# 2_POWER.net
KiCad netlist of a schematic drawn in Altium Designer
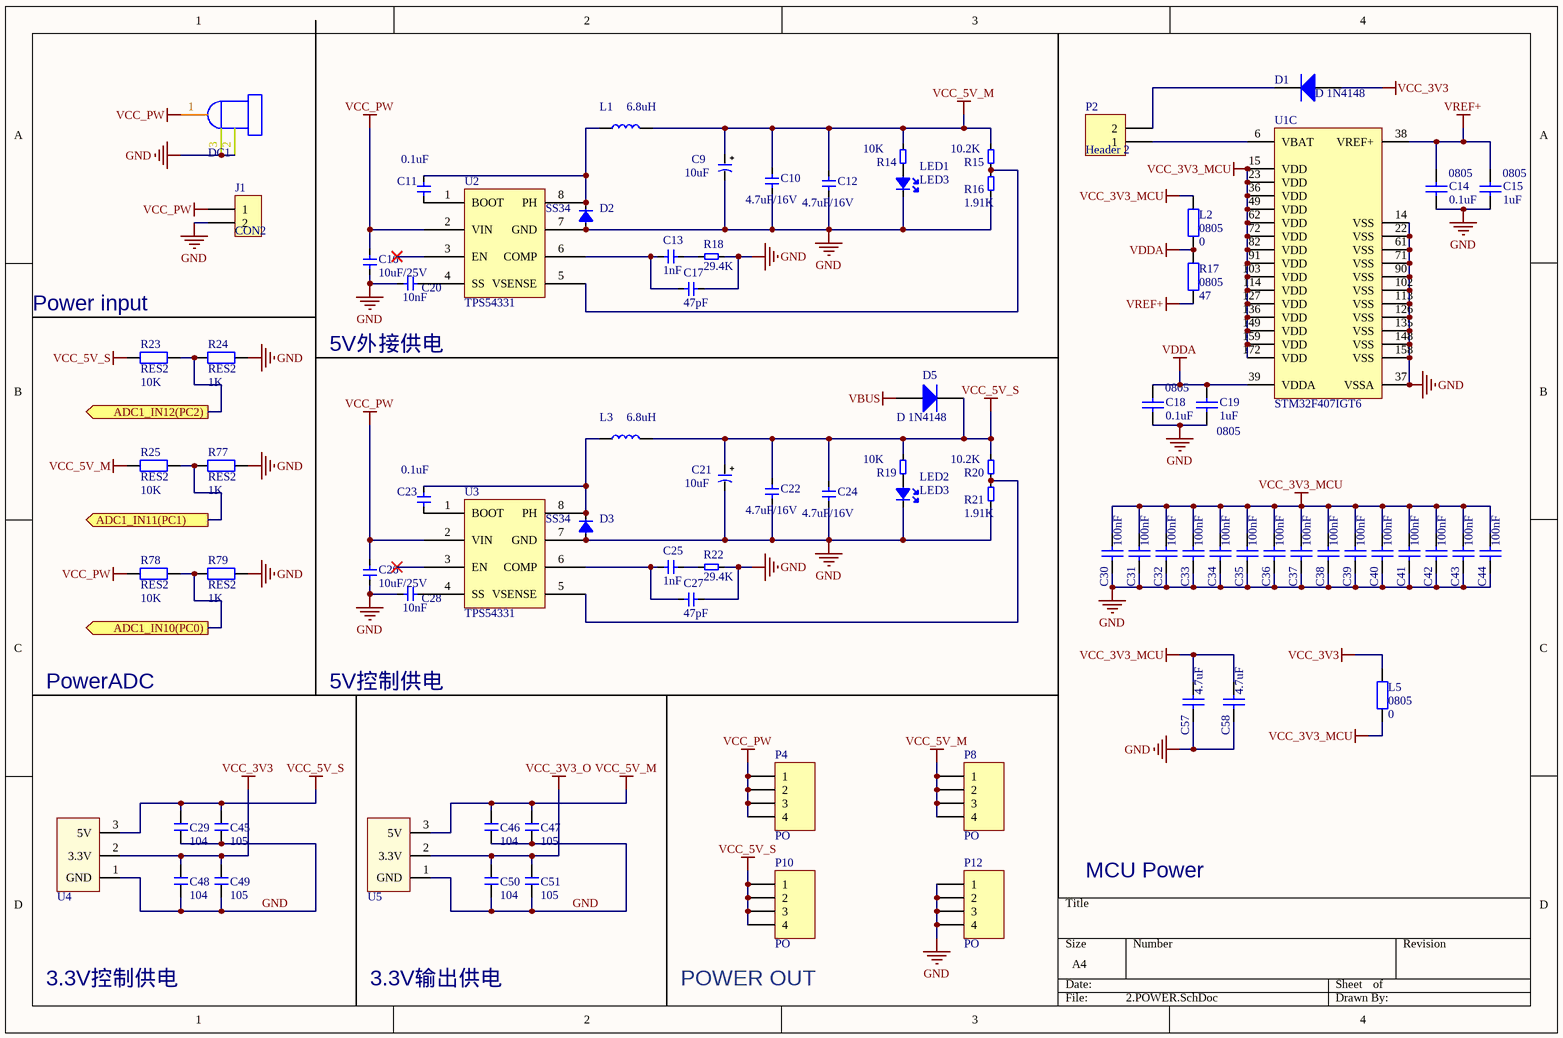
[diagram p0: 2.POWER.SchDoc]

(export (version "E")
  (design (tool "Eeschema 10.0.6"))
  (components
    (comp (ref "C9")
      (value "10uF")
      (footprint "3528")
      (description "Capacitor")
      (libsource (lib "YHT-SCH") (part "CAP-+"))
    )
    (comp (ref "C10")
      (value "4.7uF/16V")
      (footprint "0603C")
      (description "Capacitor")
      (libsource (lib "YHT-PCB") (part "CAP"))
    )
    (comp (ref "C11")
      (value "0.1uF")
      (footprint "0603C")
      (description "Capacitor")
      (libsource (lib "HXT-SCH") (part "CAP1"))
    )
    (comp (ref "C12")
      (value "4.7uF/16V")
      (footprint "0603C")
      (description "Capacitor")
      (libsource (lib "YHT-PCB") (part "CAP"))
    )
    (comp (ref "C13")
      (value "1nF")
      (footprint "0603C")
      (description "Capacitor")
      (libsource (lib "HXT-SCH") (part "CAP1"))
    )
    (comp (ref "C14")
      (value "0805")
      (footprint "C 0603_L")
      (fields (field (name "ALTIUM_VALUE") "0.1uF"))
      (libsource (lib "QT") (part "CAP"))
    )
    (comp (ref "C15")
      (value "0805")
      (footprint "C 0603_L")
      (fields (field (name "ALTIUM_VALUE") "1uF"))
      (libsource (lib "QT") (part "CAP"))
    )
    (comp (ref "C16")
      (value "10uF/25V")
      (footprint "1206")
      (description "Capacitor")
      (libsource (lib "HXT-SCH") (part "CAP1"))
    )
    (comp (ref "C17")
      (value "47pF")
      (footprint "0603C")
      (description "Capacitor")
      (libsource (lib "YHT-PCB") (part "CAP"))
    )
    (comp (ref "C18")
      (value "0805")
      (footprint "C 0603_L")
      (fields (field (name "ALTIUM_VALUE") "0.1uF"))
      (libsource (lib "QT") (part "CAP"))
    )
    (comp (ref "C19")
      (value "0805")
      (footprint "C 0603_L")
      (fields (field (name "ALTIUM_VALUE") "1uF"))
      (libsource (lib "QT") (part "CAP"))
    )
    (comp (ref "C20")
      (value "10nF")
      (footprint "0603C")
      (description "Capacitor")
      (libsource (lib "YHT-PCB") (part "CAP"))
    )
    (comp (ref "C21")
      (value "10uF")
      (footprint "3528")
      (description "Capacitor")
      (libsource (lib "YHT-SCH") (part "CAP-+"))
    )
    (comp (ref "C22")
      (value "4.7uF/16V")
      (footprint "0603C")
      (description "Capacitor")
      (libsource (lib "YHT-PCB") (part "CAP"))
    )
    (comp (ref "C23")
      (value "0.1uF")
      (footprint "0603C")
      (description "Capacitor")
      (libsource (lib "HXT-SCH") (part "CAP1"))
    )
    (comp (ref "C24")
      (value "4.7uF/16V")
      (footprint "0603C")
      (description "Capacitor")
      (libsource (lib "YHT-PCB") (part "CAP"))
    )
    (comp (ref "C25")
      (value "1nF")
      (footprint "0603C")
      (description "Capacitor")
      (libsource (lib "HXT-SCH") (part "CAP1"))
    )
    (comp (ref "C26")
      (value "10uF/25V")
      (footprint "1206")
      (description "Capacitor")
      (libsource (lib "HXT-SCH") (part "CAP1"))
    )
    (comp (ref "C27")
      (value "47pF")
      (footprint "0603C")
      (description "Capacitor")
      (libsource (lib "YHT-PCB") (part "CAP"))
    )
    (comp (ref "C28")
      (value "10nF")
      (footprint "0603C")
      (description "Capacitor")
      (libsource (lib "YHT-PCB") (part "CAP"))
    )
    (comp (ref "C29")
      (value "104")
      (footprint "C 0805")
      (description "无极性贴片电容")
      (fields (field (name "版权归属") "源创客"))
      (libsource (lib "电阻-电容-电感") (part "C"))
    )
    (comp (ref "C30")
      (value "100nF")
      (footprint "C 0603_L")
      (fields (field (name "Comment") "0805"))
      (libsource (lib "QT") (part "CAP"))
    )
    (comp (ref "C31")
      (value "100nF")
      (footprint "C 0603_L")
      (fields (field (name "Comment") "0805"))
      (libsource (lib "QT") (part "CAP"))
    )
    (comp (ref "C32")
      (value "100nF")
      (footprint "C 0603_L")
      (fields (field (name "Comment") "0805"))
      (libsource (lib "QT") (part "CAP"))
    )
    (comp (ref "C33")
      (value "100nF")
      (footprint "C 0603_L")
      (fields (field (name "Comment") "0805"))
      (libsource (lib "QT") (part "CAP"))
    )
    (comp (ref "C34")
      (value "100nF")
      (footprint "C 0603_L")
      (fields (field (name "Comment") "0805"))
      (libsource (lib "QT") (part "CAP"))
    )
    (comp (ref "C35")
      (value "100nF")
      (footprint "C 0603_L")
      (fields (field (name "Comment") "0805"))
      (libsource (lib "QT") (part "CAP"))
    )
    (comp (ref "C36")
      (value "100nF")
      (footprint "C 0603_L")
      (fields (field (name "Comment") "0805"))
      (libsource (lib "QT") (part "CAP"))
    )
    (comp (ref "C37")
      (value "100nF")
      (footprint "C 0603_L")
      (fields (field (name "Comment") "0805"))
      (libsource (lib "QT") (part "CAP"))
    )
    (comp (ref "C38")
      (value "100nF")
      (footprint "C 0603_L")
      (fields (field (name "Comment") "0805"))
      (libsource (lib "QT") (part "CAP"))
    )
    (comp (ref "C39")
      (value "100nF")
      (footprint "C 0603_L")
      (fields (field (name "Comment") "0805"))
      (libsource (lib "QT") (part "CAP"))
    )
    (comp (ref "C40")
      (value "100nF")
      (footprint "C 0603_L")
      (fields (field (name "Comment") "0805"))
      (libsource (lib "QT") (part "CAP"))
    )
    (comp (ref "C41")
      (value "100nF")
      (footprint "C 0603_L")
      (fields (field (name "Comment") "0805"))
      (libsource (lib "QT") (part "CAP"))
    )
    (comp (ref "C42")
      (value "100nF")
      (footprint "C 0603_L")
      (fields (field (name "Comment") "0805"))
      (libsource (lib "QT") (part "CAP"))
    )
    (comp (ref "C43")
      (value "100nF")
      (footprint "C 0603_L")
      (fields (field (name "Comment") "0805"))
      (libsource (lib "QT") (part "CAP"))
    )
    (comp (ref "C44")
      (value "100nF")
      (footprint "C 0603_L")
      (fields (field (name "Comment") "0805"))
      (libsource (lib "QT") (part "CAP"))
    )
    (comp (ref "C45")
      (value "105")
      (footprint "C 0805")
      (description "无极性贴片电容")
      (fields (field (name "版权归属") "源创客"))
      (libsource (lib "电阻-电容-电感") (part "C"))
    )
    (comp (ref "C46")
      (value "104")
      (footprint "C 0805")
      (description "无极性贴片电容")
      (fields (field (name "版权归属") "源创客"))
      (libsource (lib "电阻-电容-电感") (part "C"))
    )
    (comp (ref "C47")
      (value "105")
      (footprint "C 0805")
      (description "无极性贴片电容")
      (fields (field (name "版权归属") "源创客"))
      (libsource (lib "电阻-电容-电感") (part "C"))
    )
    (comp (ref "C48")
      (value "104")
      (footprint "C 0805")
      (description "无极性贴片电容")
      (fields (field (name "版权归属") "源创客"))
      (libsource (lib "电阻-电容-电感") (part "C"))
    )
    (comp (ref "C49")
      (value "105")
      (footprint "C 0805")
      (description "无极性贴片电容")
      (fields (field (name "版权归属") "源创客"))
      (libsource (lib "电阻-电容-电感") (part "C"))
    )
    (comp (ref "C50")
      (value "104")
      (footprint "C 0805")
      (description "无极性贴片电容")
      (fields (field (name "版权归属") "源创客"))
      (libsource (lib "电阻-电容-电感") (part "C"))
    )
    (comp (ref "C51")
      (value "105")
      (footprint "C 0805")
      (description "无极性贴片电容")
      (fields (field (name "版权归属") "源创客"))
      (libsource (lib "电阻-电容-电感") (part "C"))
    )
    (comp (ref "C57")
      (value "4.7uF")
      (footprint "C 0805_M")
      (fields (field (name "Comment") "0805"))
      (libsource (lib "QT") (part "CAP"))
    )
    (comp (ref "C58")
      (value "4.7uF")
      (footprint "C 0805_M")
      (fields (field (name "Comment") "0805"))
      (libsource (lib "QT") (part "CAP"))
    )
    (comp (ref "D1")
      (value "D 1N4148")
      (footprint "SOD-523")
      (description "High Conductance Fast Diode")
      (fields (field (name "PUBLISHER") "Altium Limited"))
      (libsource (lib "QT") (part "D 1N4148"))
    )
    (comp (ref "D2")
      (value "SS34")
      (footprint "DO-214AC-SMA")
      (description "DIODE LED")
      (libsource (lib "HXT-SCH") (part "DIOLED_1"))
    )
    (comp (ref "D3")
      (value "SS34")
      (footprint "DO-214AC-SMA")
      (description "DIODE LED")
      (libsource (lib "HXT-SCH") (part "DIOLED_1"))
    )
    (comp (ref "D5")
      (value "D 1N4148")
      (footprint "SOD-123")
      (description "High Conductance Fast Diode")
      (fields (field (name "PUBLISHER") "Altium Limited"))
      (libsource (lib "QT") (part "D 1N4148"))
    )
    (comp (ref "DC1") (value "DC") (footprint "DC-005") (libsource (lib "QT") (part "DC")))
    (comp (ref "J1") (value "CON2") (footprint "DG1282-5.0") (libsource (lib "常用元件库") (part "CON2")))
    (comp (ref "L1") (value "6.8uH") (footprint "L100") (libsource (lib "HXT-SCH") (part "INDUCTOR1_1")))
    (comp (ref "L2")
      (value "0805")
      (footprint "R 0402_L")
      (description "Resistor")
      (fields (field (name "ALTIUM_VALUE") "0") (field (name "PUBLISHER") "Altium Limited"))
      (libsource (lib "QT") (part "RES2"))
    )
    (comp (ref "L3") (value "6.8uH") (footprint "L100") (libsource (lib "HXT-SCH") (part "INDUCTOR1_1")))
    (comp (ref "L5")
      (value "0805")
      (footprint "R 0805_L")
      (description "Resistor")
      (fields (field (name "ALTIUM_VALUE") "0") (field (name "PUBLISHER") "Altium Limited"))
      (libsource (lib "QT") (part "RES2"))
    )
    (comp (ref "LED1")
      (value "LED3")
      (footprint "0603-led")
      (description "DIODE LED")
      (libsource (lib "HXT-SCH") (part "CP_DIOLED"))
    )
    (comp (ref "LED2")
      (value "LED3")
      (footprint "0603-led")
      (description "DIODE LED")
      (libsource (lib "HXT-SCH") (part "CP_DIOLED"))
    )
    (comp (ref "P2")
      (value "Header 2")
      (footprint "HDR2.54-LI-2P")
      (description "Header, 2-Pin")
      (fields (field (name "PUBLISHER") "Altium Limited"))
      (libsource (lib "QT") (part "Header 2"))
    )
    (comp (ref "P4")
      (value "PO")
      (footprint "KF2EDGK-2.54-WI-4P")
      (description "Header, 4-Pin")
      (fields (field (name "PUBLISHER") "Altium Limited"))
      (libsource (lib "QT") (part "Header 4"))
    )
    (comp (ref "P8")
      (value "PO")
      (footprint "KF2EDGK-2.54-WI-4P")
      (description "Header, 4-Pin")
      (fields (field (name "PUBLISHER") "Altium Limited"))
      (libsource (lib "QT") (part "Header 4"))
    )
    (comp (ref "P10")
      (value "PO")
      (footprint "KF2EDGK-2.54-WI-4P")
      (description "Header, 4-Pin")
      (fields (field (name "PUBLISHER") "Altium Limited"))
      (libsource (lib "QT") (part "Header 4"))
    )
    (comp (ref "P12")
      (value "PO")
      (footprint "KF2EDGK-2.54-WI-4P")
      (description "Header, 4-Pin")
      (fields (field (name "PUBLISHER") "Altium Limited"))
      (libsource (lib "QT") (part "Header 4"))
    )
    (comp (ref "R14") (value "10K") (footprint "0603") (libsource (lib "HXT-SCH") (part "RES2")))
    (comp (ref "R15") (value "10.2K") (footprint "0603") (libsource (lib "HXT-SCH") (part "RES2")))
    (comp (ref "R16") (value "1.91K") (footprint "0603") (libsource (lib "HXT-SCH") (part "RES2")))
    (comp (ref "R17")
      (value "0805")
      (footprint "R 0402_L")
      (description "Resistor")
      (fields (field (name "ALTIUM_VALUE") "47") (field (name "PUBLISHER") "Altium Limited"))
      (libsource (lib "QT") (part "RES2"))
    )
    (comp (ref "R18") (value "29.4K") (footprint "0603") (libsource (lib "HXT-SCH") (part "RES2")))
    (comp (ref "R19") (value "10K") (footprint "0603") (libsource (lib "HXT-SCH") (part "RES2")))
    (comp (ref "R20") (value "10.2K") (footprint "0603") (libsource (lib "HXT-SCH") (part "RES2")))
    (comp (ref "R21") (value "1.91K") (footprint "0603") (libsource (lib "HXT-SCH") (part "RES2")))
    (comp (ref "R22") (value "29.4K") (footprint "0603") (libsource (lib "HXT-SCH") (part "RES2")))
    (comp (ref "R23")
      (value "RES2")
      (footprint "R 0805_L")
      (description "Resistor")
      (fields (field (name "ALTIUM_VALUE") "10K") (field (name "PUBLISHER") "Altium Limited"))
      (libsource (lib "") (part "RES2_1"))
    )
    (comp (ref "R24")
      (value "RES2")
      (footprint "R 0805_L")
      (description "Resistor")
      (fields (field (name "ALTIUM_VALUE") "1K") (field (name "PUBLISHER") "Altium Limited"))
      (libsource (lib "") (part "RES2_1"))
    )
    (comp (ref "R25")
      (value "RES2")
      (footprint "R 0805_L")
      (description "Resistor")
      (fields (field (name "ALTIUM_VALUE") "10K") (field (name "PUBLISHER") "Altium Limited"))
      (libsource (lib "") (part "RES2_1"))
    )
    (comp (ref "R77")
      (value "RES2")
      (footprint "R 0805_L")
      (description "Resistor")
      (fields (field (name "ALTIUM_VALUE") "1K") (field (name "PUBLISHER") "Altium Limited"))
      (libsource (lib "") (part "RES2_1"))
    )
    (comp (ref "R78")
      (value "RES2")
      (footprint "R 0805_L")
      (description "Resistor")
      (fields (field (name "ALTIUM_VALUE") "10K") (field (name "PUBLISHER") "Altium Limited"))
      (libsource (lib "") (part "RES2_1"))
    )
    (comp (ref "R79")
      (value "RES2")
      (footprint "R 0805_L")
      (description "Resistor")
      (fields (field (name "ALTIUM_VALUE") "1K") (field (name "PUBLISHER") "Altium Limited"))
      (libsource (lib "") (part "RES2_1"))
    )
    (comp (ref "U1")
      (value "STM32F407IGT6")
      (footprint "STM-LQFP176_N")
      (fields (field (name "MANUFACTURER") "STMicroelectronics"))
      (libsource (lib "STMicroelectronics STM32 F4") (part "STM32F407IGT6"))
    )
    (comp (ref "U2") (value "TPS54331") (footprint "SO08") (libsource (lib "YHT-SCH") (part "TPS54331")))
    (comp (ref "U3") (value "TPS54331") (footprint "SO08") (libsource (lib "YHT-SCH") (part "TPS54331")))
    (comp (ref "U4") (value "LM1117") (footprint "SOT223") (libsource (lib "常用元件库") (part "LM1117")))
    (comp (ref "U5") (value "LM1117") (footprint "SOT223") (libsource (lib "常用元件库") (part "LM1117")))
  )
  (nets
    (net (code "1") (name "/ADC1_IN10(PC0)") (class "Default")
      (node (ref "R78") (pin "1") (pinfunction "1_1") (pintype "passive"))
      (node (ref "R79") (pin "2") (pinfunction "2_2") (pintype "passive"))
    )
    (net (code "2") (name "/ADC1_IN11(PC1)") (class "Default")
      (node (ref "R25") (pin "1") (pinfunction "1_1") (pintype "passive"))
      (node (ref "R77") (pin "2") (pinfunction "2_2") (pintype "passive"))
    )
    (net (code "3") (name "/ADC1_IN12(PC2)") (class "Default")
      (node (ref "R23") (pin "1") (pinfunction "1_1") (pintype "passive"))
      (node (ref "R24") (pin "2") (pinfunction "2_2") (pintype "passive"))
    )
    (net (code "4") (name "GND") (class "Default")
      (node (ref "C10") (pin "1") (pinfunction "1_1") (pintype "passive"))
      (node (ref "C12") (pin "1") (pinfunction "1_1") (pintype "passive"))
      (node (ref "C14") (pin "1") (pinfunction "1_1") (pintype "passive"))
      (node (ref "C15") (pin "1") (pinfunction "1_1") (pintype "passive"))
      (node (ref "C16") (pin "1") (pinfunction "1_1") (pintype "passive"))
      (node (ref "C17") (pin "2") (pinfunction "2_2") (pintype "passive"))
      (node (ref "C18") (pin "1") (pinfunction "1_1") (pintype "passive"))
      (node (ref "C19") (pin "1") (pinfunction "1_1") (pintype "passive"))
      (node (ref "C20") (pin "2") (pinfunction "2_2") (pintype "passive"))
      (node (ref "C21") (pin "2") (pinfunction "2_2") (pintype "passive"))
      (node (ref "C22") (pin "1") (pinfunction "1_1") (pintype "passive"))
      (node (ref "C24") (pin "1") (pinfunction "1_1") (pintype "passive"))
      (node (ref "C26") (pin "1") (pinfunction "1_1") (pintype "passive"))
      (node (ref "C27") (pin "2") (pinfunction "2_2") (pintype "passive"))
      (node (ref "C28") (pin "2") (pinfunction "2_2") (pintype "passive"))
      (node (ref "C29") (pin "1") (pinfunction "1_1") (pintype "passive"))
      (node (ref "C30") (pin "1") (pinfunction "1_1") (pintype "passive"))
      (node (ref "C31") (pin "1") (pinfunction "1_1") (pintype "passive"))
      (node (ref "C32") (pin "1") (pinfunction "1_1") (pintype "passive"))
      (node (ref "C33") (pin "1") (pinfunction "1_1") (pintype "passive"))
      (node (ref "C34") (pin "1") (pinfunction "1_1") (pintype "passive"))
      (node (ref "C35") (pin "1") (pinfunction "1_1") (pintype "passive"))
      (node (ref "C36") (pin "1") (pinfunction "1_1") (pintype "passive"))
      (node (ref "C37") (pin "1") (pinfunction "1_1") (pintype "passive"))
      (node (ref "C38") (pin "1") (pinfunction "1_1") (pintype "passive"))
      (node (ref "C39") (pin "1") (pinfunction "1_1") (pintype "passive"))
      (node (ref "C40") (pin "1") (pinfunction "1_1") (pintype "passive"))
      (node (ref "C41") (pin "1") (pinfunction "1_1") (pintype "passive"))
      (node (ref "C42") (pin "1") (pinfunction "1_1") (pintype "passive"))
      (node (ref "C43") (pin "1") (pinfunction "1_1") (pintype "passive"))
      (node (ref "C44") (pin "1") (pinfunction "1_1") (pintype "passive"))
      (node (ref "C45") (pin "2") (pinfunction "2_2") (pintype "passive"))
      (node (ref "C46") (pin "1") (pinfunction "1_1") (pintype "passive"))
      (node (ref "C47") (pin "2") (pinfunction "2_2") (pintype "passive"))
      (node (ref "C48") (pin "1") (pinfunction "1_1") (pintype "passive"))
      (node (ref "C49") (pin "2") (pinfunction "2_2") (pintype "passive"))
      (node (ref "C50") (pin "1") (pinfunction "1_1") (pintype "passive"))
      (node (ref "C51") (pin "2") (pinfunction "2_2") (pintype "passive"))
      (node (ref "C57") (pin "1") (pinfunction "1_1") (pintype "passive"))
      (node (ref "C58") (pin "1") (pinfunction "1_1") (pintype "passive"))
      (node (ref "C9") (pin "2") (pinfunction "2_2") (pintype "passive"))
      (node (ref "D2") (pin "1") (pinfunction "A_1") (pintype "passive"))
      (node (ref "D3") (pin "1") (pinfunction "A_1") (pintype "passive"))
      (node (ref "DC1") (pin "2") (pinfunction "-_2") (pintype "passive"))
      (node (ref "DC1") (pin "3") (pinfunction "-_3") (pintype "passive"))
      (node (ref "J1") (pin "2") (pinfunction "2_2") (pintype "passive"))
      (node (ref "LED1") (pin "2") (pinfunction "K_2") (pintype "passive"))
      (node (ref "LED2") (pin "2") (pinfunction "K_2") (pintype "passive"))
      (node (ref "P12") (pin "1") (pinfunction "1_1") (pintype "passive"))
      (node (ref "P12") (pin "2") (pinfunction "2_2") (pintype "passive"))
      (node (ref "P12") (pin "3") (pinfunction "3_3") (pintype "passive"))
      (node (ref "P12") (pin "4") (pinfunction "4_4") (pintype "passive"))
      (node (ref "R16") (pin "1") (pinfunction "1_1") (pintype "passive"))
      (node (ref "R18") (pin "1") (pinfunction "1_1") (pintype "passive"))
      (node (ref "R21") (pin "1") (pinfunction "1_1") (pintype "passive"))
      (node (ref "R22") (pin "1") (pinfunction "1_1") (pintype "passive"))
      (node (ref "R24") (pin "1") (pinfunction "1_1") (pintype "passive"))
      (node (ref "R77") (pin "1") (pinfunction "1_1") (pintype "passive"))
      (node (ref "R79") (pin "1") (pinfunction "1_1") (pintype "passive"))
      (node (ref "U1") (pin "102") (pinfunction "VSS_102") (pintype "power_in"))
      (node (ref "U1") (pin "113") (pinfunction "VSS_113") (pintype "power_in"))
      (node (ref "U1") (pin "126") (pinfunction "VSS_126") (pintype "power_in"))
      (node (ref "U1") (pin "135") (pinfunction "VSS_135") (pintype "power_in"))
      (node (ref "U1") (pin "14") (pinfunction "VSS_14") (pintype "power_in"))
      (node (ref "U1") (pin "148") (pinfunction "VSS_148") (pintype "power_in"))
      (node (ref "U1") (pin "158") (pinfunction "VSS_158") (pintype "power_in"))
      (node (ref "U1") (pin "22") (pinfunction "VSS_22") (pintype "power_in"))
      (node (ref "U1") (pin "37") (pinfunction "VSSA_37") (pintype "power_in"))
      (node (ref "U1") (pin "61") (pinfunction "VSS_61") (pintype "power_in"))
      (node (ref "U1") (pin "71") (pinfunction "VSS_71") (pintype "power_in"))
      (node (ref "U1") (pin "90") (pinfunction "VSS_90") (pintype "power_in"))
      (node (ref "U2") (pin "7") (pinfunction "GND_7") (pintype "passive"))
      (node (ref "U3") (pin "7") (pinfunction "GND_7") (pintype "passive"))
      (node (ref "U4") (pin "1") (pinfunction "GND_1") (pintype "passive"))
      (node (ref "U5") (pin "1") (pinfunction "GND_1") (pintype "passive"))
    )
    (net (code "5") (name "Net-(C13-Pad1)") (class "Default")
      (node (ref "C13") (pin "1") (pinfunction "1_1") (pintype "passive"))
      (node (ref "R18") (pin "2") (pinfunction "2_2") (pintype "passive"))
    )
    (net (code "6") (name "Net-(C25-Pad1)") (class "Default")
      (node (ref "C25") (pin "1") (pinfunction "1_1") (pintype "passive"))
      (node (ref "R22") (pin "2") (pinfunction "2_2") (pintype "passive"))
    )
    (net (code "7") (name "Net-(D1-K)") (class "Default")
      (node (ref "D1") (pin "2") (pinfunction "K_2") (pintype "passive"))
      (node (ref "P2") (pin "2") (pinfunction "2_2") (pintype "passive"))
    )
    (net (code "8") (name "Net-(D2-K)") (class "Default")
      (node (ref "C11") (pin "2") (pinfunction "2_2") (pintype "passive"))
      (node (ref "D2") (pin "2") (pinfunction "K_2") (pintype "passive"))
      (node (ref "L1") (pin "2") (pinfunction "2_2") (pintype "passive"))
      (node (ref "U2") (pin "8") (pinfunction "PH_8") (pintype "power_in"))
    )
    (net (code "9") (name "Net-(D3-K)") (class "Default")
      (node (ref "C23") (pin "2") (pinfunction "2_2") (pintype "passive"))
      (node (ref "D3") (pin "2") (pinfunction "K_2") (pintype "passive"))
      (node (ref "L3") (pin "2") (pinfunction "2_2") (pintype "passive"))
      (node (ref "U3") (pin "8") (pinfunction "PH_8") (pintype "power_in"))
    )
    (net (code "10") (name "Net-(LED1-A)") (class "Default")
      (node (ref "LED1") (pin "1") (pinfunction "A_1") (pintype "passive"))
      (node (ref "R14") (pin "1") (pinfunction "1_1") (pintype "passive"))
    )
    (net (code "11") (name "Net-(LED2-A)") (class "Default")
      (node (ref "LED2") (pin "1") (pinfunction "A_1") (pintype "passive"))
      (node (ref "R19") (pin "1") (pinfunction "1_1") (pintype "passive"))
    )
    (net (code "12") (name "Net-(U1C-VBAT)") (class "Default")
      (node (ref "P2") (pin "1") (pinfunction "1_1") (pintype "passive"))
      (node (ref "U1") (pin "6") (pinfunction "VBAT_6") (pintype "power_in"))
    )
    (net (code "13") (name "Net-(U2-BOOT)") (class "Default")
      (node (ref "C11") (pin "1") (pinfunction "1_1") (pintype "passive"))
      (node (ref "U2") (pin "1") (pinfunction "BOOT_1") (pintype "passive"))
    )
    (net (code "14") (name "Net-(U2-COMP)") (class "Default")
      (node (ref "C13") (pin "2") (pinfunction "2_2") (pintype "passive"))
      (node (ref "C17") (pin "1") (pinfunction "1_1") (pintype "passive"))
      (node (ref "U2") (pin "6") (pinfunction "COMP_6") (pintype "passive"))
    )
    (net (code "15") (name "Net-(U2-SS)") (class "Default")
      (node (ref "C20") (pin "1") (pinfunction "1_1") (pintype "passive"))
      (node (ref "U2") (pin "4") (pinfunction "SS_4") (pintype "power_in"))
    )
    (net (code "16") (name "Net-(U2-VSENSE)") (class "Default")
      (node (ref "R15") (pin "1") (pinfunction "1_1") (pintype "passive"))
      (node (ref "R16") (pin "2") (pinfunction "2_2") (pintype "passive"))
      (node (ref "U2") (pin "5") (pinfunction "VSENSE_5") (pintype "passive"))
    )
    (net (code "17") (name "Net-(U3-BOOT)") (class "Default")
      (node (ref "C23") (pin "1") (pinfunction "1_1") (pintype "passive"))
      (node (ref "U3") (pin "1") (pinfunction "BOOT_1") (pintype "passive"))
    )
    (net (code "18") (name "Net-(U3-COMP)") (class "Default")
      (node (ref "C25") (pin "2") (pinfunction "2_2") (pintype "passive"))
      (node (ref "C27") (pin "1") (pinfunction "1_1") (pintype "passive"))
      (node (ref "U3") (pin "6") (pinfunction "COMP_6") (pintype "passive"))
    )
    (net (code "19") (name "Net-(U3-SS)") (class "Default")
      (node (ref "C28") (pin "1") (pinfunction "1_1") (pintype "passive"))
      (node (ref "U3") (pin "4") (pinfunction "SS_4") (pintype "power_in"))
    )
    (net (code "20") (name "Net-(U3-VSENSE)") (class "Default")
      (node (ref "R20") (pin "1") (pinfunction "1_1") (pintype "passive"))
      (node (ref "R21") (pin "2") (pinfunction "2_2") (pintype "passive"))
      (node (ref "U3") (pin "5") (pinfunction "VSENSE_5") (pintype "passive"))
    )
    (net (code "21") (name "VBUS") (class "Default")
      (node (ref "D5") (pin "1") (pinfunction "A_1") (pintype "passive"))
    )
    (net (code "22") (name "VCC_3V3") (class "Default")
      (node (ref "C48") (pin "2") (pinfunction "2_2") (pintype "passive"))
      (node (ref "C49") (pin "1") (pinfunction "1_1") (pintype "passive"))
      (node (ref "D1") (pin "1") (pinfunction "A_1") (pintype "passive"))
      (node (ref "L5") (pin "2") (pinfunction "2_2") (pintype "passive"))
      (node (ref "U4") (pin "2") (pinfunction "3.3V_2") (pintype "passive"))
    )
    (net (code "23") (name "VCC_3V3_MCU") (class "Default")
      (node (ref "C30") (pin "2") (pinfunction "2_2") (pintype "passive"))
      (node (ref "C31") (pin "2") (pinfunction "2_2") (pintype "passive"))
      (node (ref "C32") (pin "2") (pinfunction "2_2") (pintype "passive"))
      (node (ref "C33") (pin "2") (pinfunction "2_2") (pintype "passive"))
      (node (ref "C34") (pin "2") (pinfunction "2_2") (pintype "passive"))
      (node (ref "C35") (pin "2") (pinfunction "2_2") (pintype "passive"))
      (node (ref "C36") (pin "2") (pinfunction "2_2") (pintype "passive"))
      (node (ref "C37") (pin "2") (pinfunction "2_2") (pintype "passive"))
      (node (ref "C38") (pin "2") (pinfunction "2_2") (pintype "passive"))
      (node (ref "C39") (pin "2") (pinfunction "2_2") (pintype "passive"))
      (node (ref "C40") (pin "2") (pinfunction "2_2") (pintype "passive"))
      (node (ref "C41") (pin "2") (pinfunction "2_2") (pintype "passive"))
      (node (ref "C42") (pin "2") (pinfunction "2_2") (pintype "passive"))
      (node (ref "C43") (pin "2") (pinfunction "2_2") (pintype "passive"))
      (node (ref "C44") (pin "2") (pinfunction "2_2") (pintype "passive"))
      (node (ref "C57") (pin "2") (pinfunction "2_2") (pintype "passive"))
      (node (ref "C58") (pin "2") (pinfunction "2_2") (pintype "passive"))
      (node (ref "L2") (pin "2") (pinfunction "2_2") (pintype "passive"))
      (node (ref "L5") (pin "1") (pinfunction "1_1") (pintype "passive"))
      (node (ref "U1") (pin "103") (pinfunction "VDD_103") (pintype "power_in"))
      (node (ref "U1") (pin "114") (pinfunction "VDD_114") (pintype "power_in"))
      (node (ref "U1") (pin "127") (pinfunction "VDD_127") (pintype "power_in"))
      (node (ref "U1") (pin "136") (pinfunction "VDD_136") (pintype "power_in"))
      (node (ref "U1") (pin "149") (pinfunction "VDD_149") (pintype "power_in"))
      (node (ref "U1") (pin "15") (pinfunction "VDD_15") (pintype "power_in"))
      (node (ref "U1") (pin "159") (pinfunction "VDD_159") (pintype "power_in"))
      (node (ref "U1") (pin "172") (pinfunction "VDD_172") (pintype "power_in"))
      (node (ref "U1") (pin "23") (pinfunction "VDD_23") (pintype "power_in"))
      (node (ref "U1") (pin "36") (pinfunction "VDD_36") (pintype "power_in"))
      (node (ref "U1") (pin "49") (pinfunction "VDD_49") (pintype "power_in"))
      (node (ref "U1") (pin "62") (pinfunction "VDD_62") (pintype "power_in"))
      (node (ref "U1") (pin "72") (pinfunction "VDD_72") (pintype "power_in"))
      (node (ref "U1") (pin "82") (pinfunction "VDD_82") (pintype "power_in"))
      (node (ref "U1") (pin "91") (pinfunction "VDD_91") (pintype "power_in"))
    )
    (net (code "24") (name "VCC_3V3_O") (class "Default")
      (node (ref "C50") (pin "2") (pinfunction "2_2") (pintype "passive"))
      (node (ref "C51") (pin "1") (pinfunction "1_1") (pintype "passive"))
      (node (ref "U5") (pin "2") (pinfunction "3.3V_2") (pintype "passive"))
    )
    (net (code "25") (name "VCC_5V_M") (class "Default")
      (node (ref "C10") (pin "2") (pinfunction "2_2") (pintype "passive"))
      (node (ref "C12") (pin "2") (pinfunction "2_2") (pintype "passive"))
      (node (ref "C46") (pin "2") (pinfunction "2_2") (pintype "passive"))
      (node (ref "C47") (pin "1") (pinfunction "1_1") (pintype "passive"))
      (node (ref "C9") (pin "1") (pinfunction "1_1") (pintype "passive"))
      (node (ref "L1") (pin "1") (pinfunction "1_1") (pintype "passive"))
      (node (ref "P8") (pin "1") (pinfunction "1_1") (pintype "passive"))
      (node (ref "P8") (pin "2") (pinfunction "2_2") (pintype "passive"))
      (node (ref "P8") (pin "3") (pinfunction "3_3") (pintype "passive"))
      (node (ref "P8") (pin "4") (pinfunction "4_4") (pintype "passive"))
      (node (ref "R14") (pin "2") (pinfunction "2_2") (pintype "passive"))
      (node (ref "R15") (pin "2") (pinfunction "2_2") (pintype "passive"))
      (node (ref "R25") (pin "2") (pinfunction "2_2") (pintype "passive"))
      (node (ref "U5") (pin "3") (pinfunction "5V_3") (pintype "passive"))
    )
    (net (code "26") (name "VCC_5V_S") (class "Default")
      (node (ref "C21") (pin "1") (pinfunction "1_1") (pintype "passive"))
      (node (ref "C22") (pin "2") (pinfunction "2_2") (pintype "passive"))
      (node (ref "C24") (pin "2") (pinfunction "2_2") (pintype "passive"))
      (node (ref "C29") (pin "2") (pinfunction "2_2") (pintype "passive"))
      (node (ref "C45") (pin "1") (pinfunction "1_1") (pintype "passive"))
      (node (ref "D5") (pin "2") (pinfunction "K_2") (pintype "passive"))
      (node (ref "L3") (pin "1") (pinfunction "1_1") (pintype "passive"))
      (node (ref "P10") (pin "1") (pinfunction "1_1") (pintype "passive"))
      (node (ref "P10") (pin "2") (pinfunction "2_2") (pintype "passive"))
      (node (ref "P10") (pin "3") (pinfunction "3_3") (pintype "passive"))
      (node (ref "P10") (pin "4") (pinfunction "4_4") (pintype "passive"))
      (node (ref "R19") (pin "2") (pinfunction "2_2") (pintype "passive"))
      (node (ref "R20") (pin "2") (pinfunction "2_2") (pintype "passive"))
      (node (ref "R23") (pin "2") (pinfunction "2_2") (pintype "passive"))
      (node (ref "U4") (pin "3") (pinfunction "5V_3") (pintype "passive"))
    )
    (net (code "27") (name "VCC_PW") (class "Default")
      (node (ref "C16") (pin "2") (pinfunction "2_2") (pintype "passive"))
      (node (ref "C26") (pin "2") (pinfunction "2_2") (pintype "passive"))
      (node (ref "DC1") (pin "1") (pinfunction "+_1") (pintype "passive"))
      (node (ref "J1") (pin "1") (pinfunction "1_1") (pintype "passive"))
      (node (ref "P4") (pin "1") (pinfunction "1_1") (pintype "passive"))
      (node (ref "P4") (pin "2") (pinfunction "2_2") (pintype "passive"))
      (node (ref "P4") (pin "3") (pinfunction "3_3") (pintype "passive"))
      (node (ref "P4") (pin "4") (pinfunction "4_4") (pintype "passive"))
      (node (ref "R78") (pin "2") (pinfunction "2_2") (pintype "passive"))
      (node (ref "U2") (pin "2") (pinfunction "VIN_2") (pintype "passive"))
      (node (ref "U3") (pin "2") (pinfunction "VIN_2") (pintype "passive"))
    )
    (net (code "28") (name "VDDA") (class "Default")
      (node (ref "C18") (pin "2") (pinfunction "2_2") (pintype "passive"))
      (node (ref "C19") (pin "2") (pinfunction "2_2") (pintype "passive"))
      (node (ref "L2") (pin "1") (pinfunction "1_1") (pintype "passive"))
      (node (ref "R17") (pin "2") (pinfunction "2_2") (pintype "passive"))
      (node (ref "U1") (pin "39") (pinfunction "VDDA_39") (pintype "power_in"))
    )
    (net (code "29") (name "VREF+") (class "Default")
      (node (ref "C14") (pin "2") (pinfunction "2_2") (pintype "passive"))
      (node (ref "C15") (pin "2") (pinfunction "2_2") (pintype "passive"))
      (node (ref "R17") (pin "1") (pinfunction "1_1") (pintype "passive"))
      (node (ref "U1") (pin "38") (pinfunction "VREF+_38") (pintype "power_in"))
    )
    (net (code "30") (name "unconnected-(U2-EN-Pad3)") (class "Default")
      (node (ref "U2") (pin "3") (pinfunction "EN_3") (pintype "passive+no_connect"))
    )
    (net (code "31") (name "unconnected-(U3-EN-Pad3)") (class "Default")
      (node (ref "U3") (pin "3") (pinfunction "EN_3") (pintype "passive+no_connect"))
    )
  )
)
